# WorkshopEth.net
KiCad netlist of a schematic drawn in EasyEDA Pro
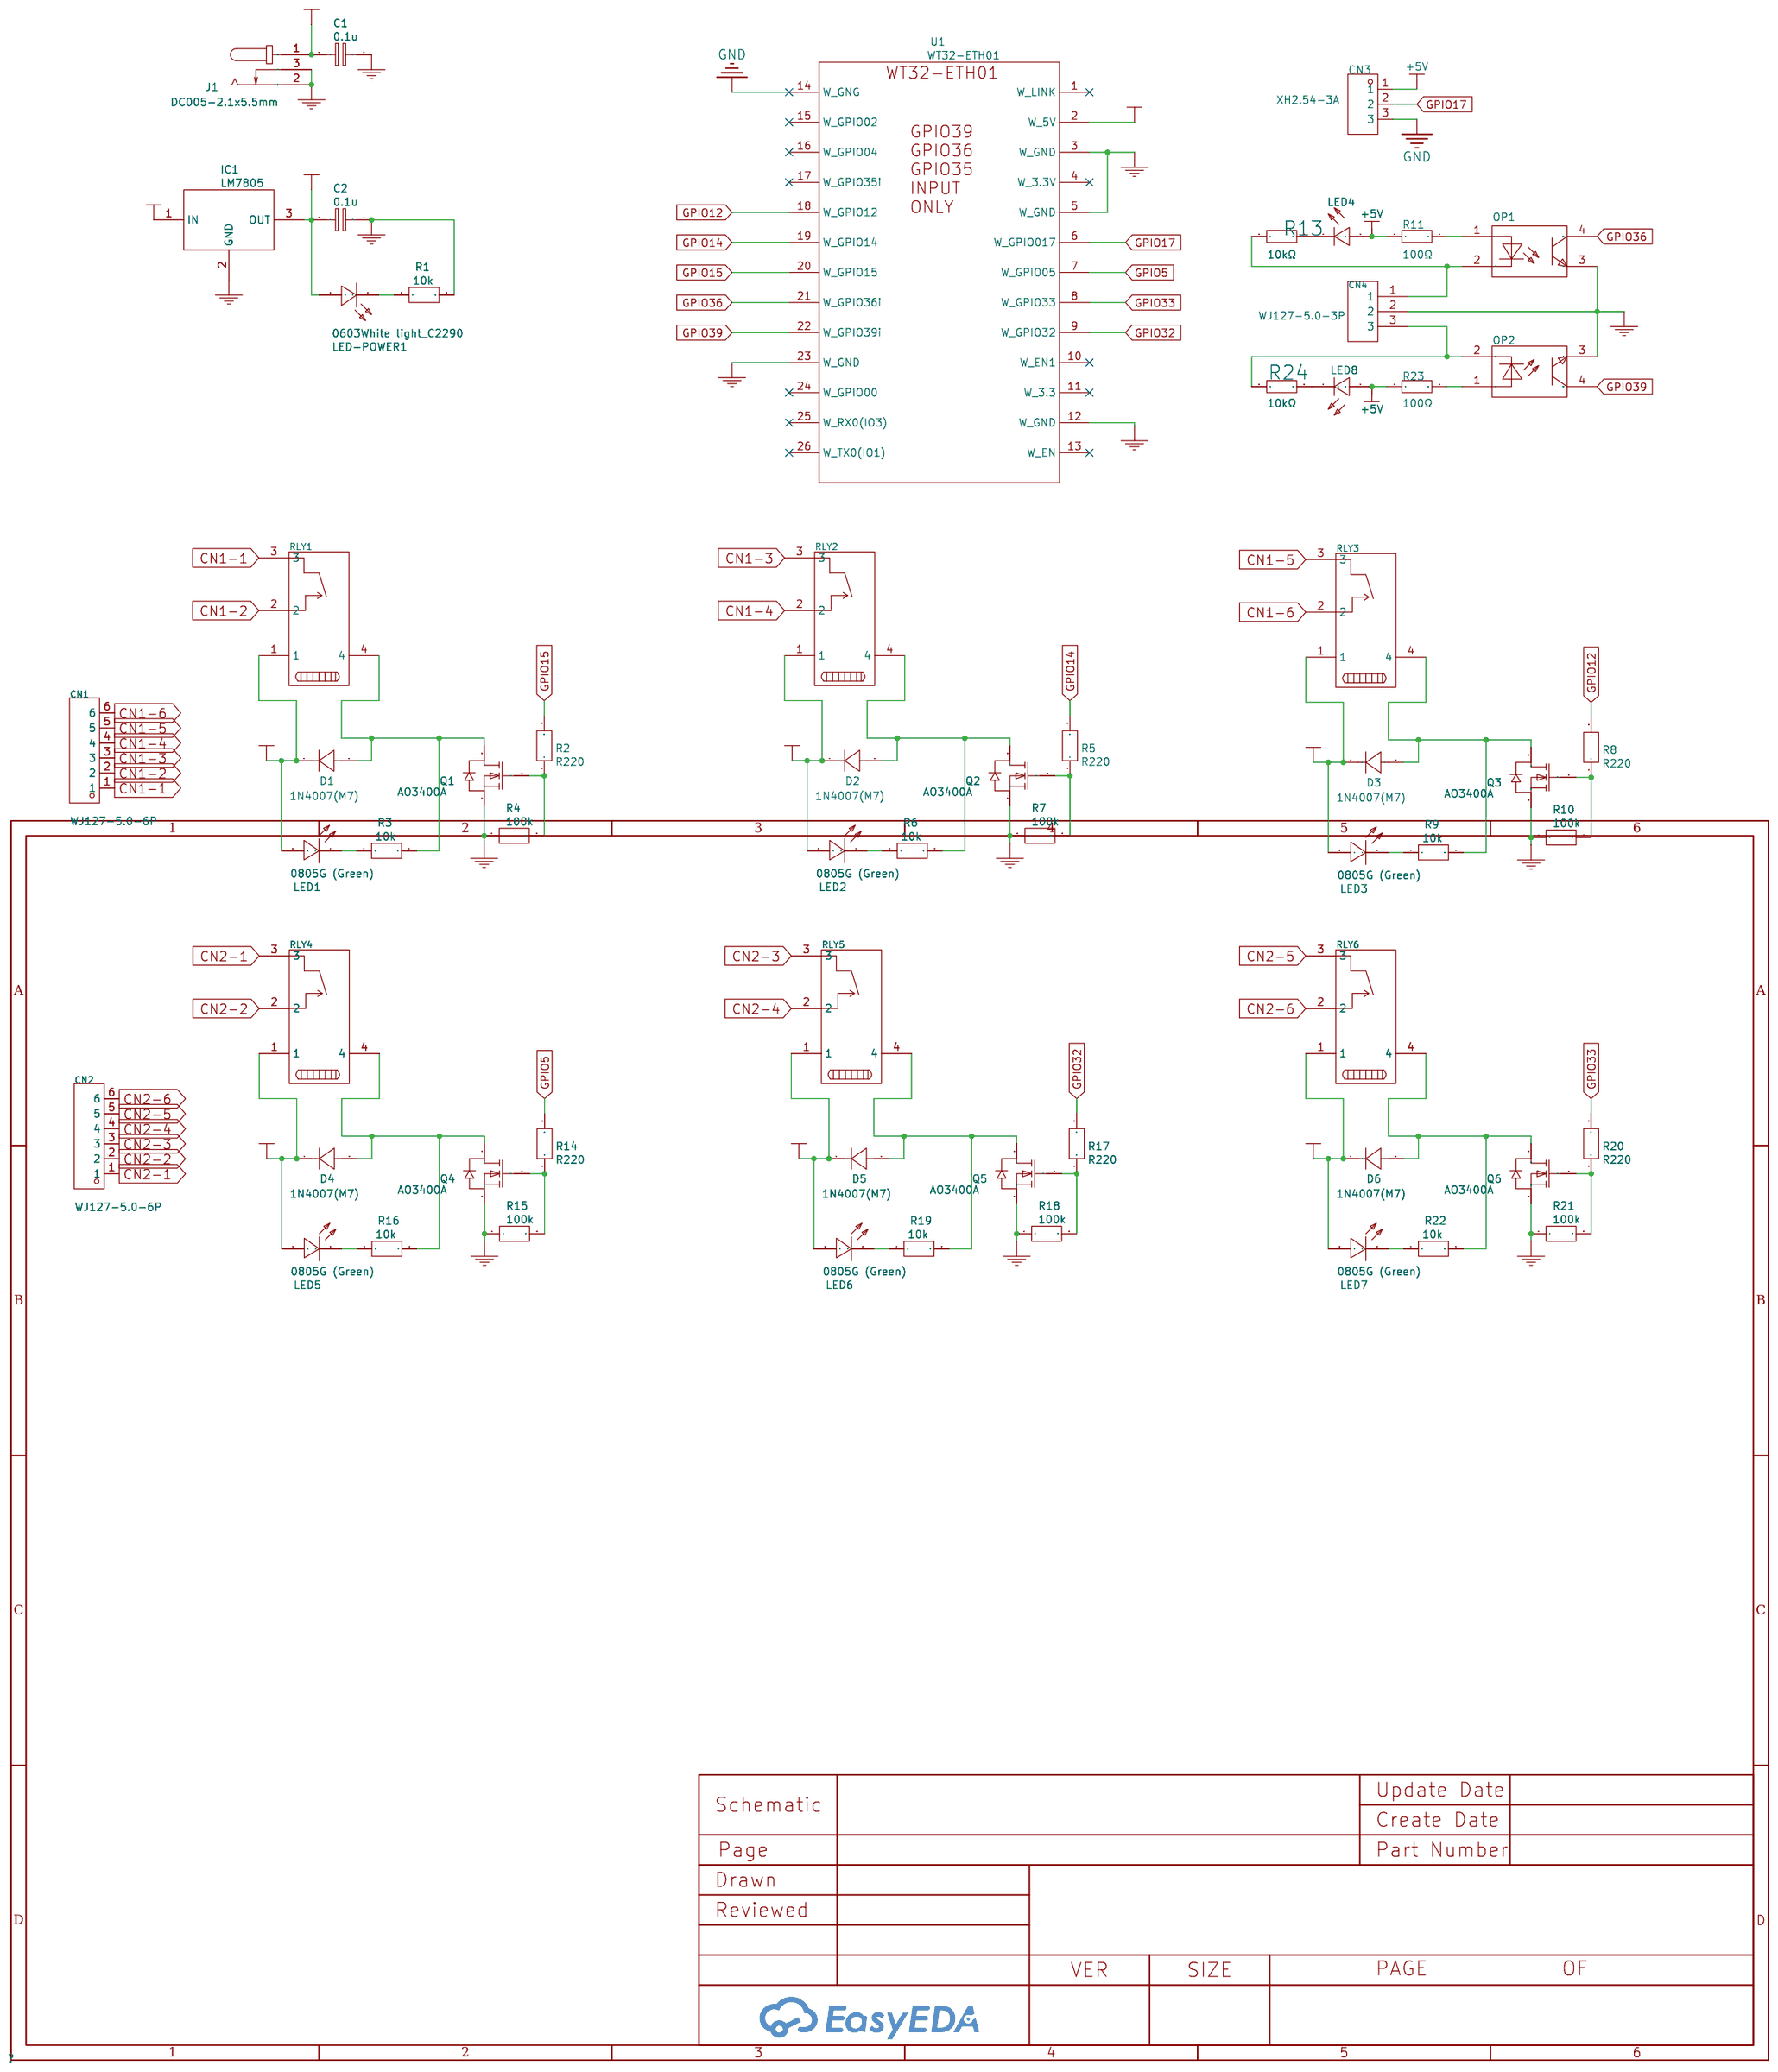
[diagram p0: schematic sheet]

(export (version "E")
  (design (tool "Eeschema 10.0.6"))
  (components
    (comp (ref "C1")
      (value "0.1u")
      (footprint "easyedapro:C0603")
      (fields
        (field (name "Manufacturer Part") "CL05B104KO5NNNC")
        (field (name "Manufacturer") "SAMSUNG(三星)")
      )
      (libsource (lib "easyedapro") (part "0.1u"))
    )
    (comp (ref "C2")
      (value "0.1u")
      (footprint "easyedapro:C0603")
      (fields
        (field (name "Manufacturer Part") "CL05B104KO5NNNC")
        (field (name "Manufacturer") "SAMSUNG(三星)")
      )
      (libsource (lib "easyedapro") (part "0.1u"))
    )
    (comp (ref "CN1")
      (value "WJ127-5.0-6P")
      (footprint "easyedapro:CONN-TH_6P-P5.00_WJ127-5.0-6P")
      (fields (field (name "Manufacturer") "KANGNEX(康奈克斯电气)"))
      (libsource (lib "easyedapro") (part "WJ127-5.0-6P"))
    )
    (comp (ref "CN2")
      (value "WJ127-5.0-6P")
      (footprint "easyedapro:CONN-TH_6P-P5.00_WJ127-5.0-6P")
      (fields (field (name "Manufacturer") "KANGNEX(康奈克斯电气)"))
      (libsource (lib "easyedapro") (part "WJ127-5.0-6P"))
    )
    (comp (ref "CN3")
      (value "XH2.54-3A")
      (footprint "easyedapro:CONN-TH_3P-P2.50_HCTL_XH-3A-L")
      (libsource (lib "easyedapro") (part "XH2.54-3A"))
    )
    (comp (ref "CN4")
      (value "WJ127-5.0-3P")
      (footprint "easyedapro:CONN-TH_3P-P5.00_WJ127-5.0-3P")
      (fields (field (name "Manufacturer") "KANGNEX(康奈克斯电气)"))
      (libsource (lib "easyedapro") (part "WJ127-5.0-3P"))
    )
    (comp (ref "D1")
      (value "1N4007(M7)")
      (footprint "easyedapro:SMA_L4.3-W2.7-LS5.1-RD")
      (fields (field (name "Manufacturer") "UMW(友台半导体)"))
      (libsource (lib "easyedapro") (part "1N4007(M7)"))
    )
    (comp (ref "D2")
      (value "1N4007(M7)")
      (footprint "easyedapro:SMA_L4.3-W2.7-LS5.1-RD")
      (fields (field (name "Manufacturer") "UMW(友台半导体)"))
      (libsource (lib "easyedapro") (part "1N4007(M7)"))
    )
    (comp (ref "D3")
      (value "1N4007(M7)")
      (footprint "easyedapro:SMA_L4.3-W2.7-LS5.1-RD")
      (fields (field (name "Manufacturer") "UMW(友台半导体)"))
      (libsource (lib "easyedapro") (part "1N4007(M7)"))
    )
    (comp (ref "D4")
      (value "1N4007(M7)")
      (footprint "easyedapro:SMA_L4.3-W2.7-LS5.1-RD")
      (fields (field (name "Manufacturer") "UMW(友台半导体)"))
      (libsource (lib "easyedapro") (part "1N4007(M7)"))
    )
    (comp (ref "D5")
      (value "1N4007(M7)")
      (footprint "easyedapro:SMA_L4.3-W2.7-LS5.1-RD")
      (fields (field (name "Manufacturer") "UMW(友台半导体)"))
      (libsource (lib "easyedapro") (part "1N4007(M7)"))
    )
    (comp (ref "D6")
      (value "1N4007(M7)")
      (footprint "easyedapro:SMA_L4.3-W2.7-LS5.1-RD")
      (fields (field (name "Manufacturer") "UMW(友台半导体)"))
      (libsource (lib "easyedapro") (part "1N4007(M7)"))
    )
    (comp (ref "IC1")
      (value "LM7805")
      (footprint "easyedapro:LM7805")
      (libsource (lib "easyedapro") (part "LM7805"))
    )
    (comp (ref "J1")
      (value "DC005-2.1x5.5mm")
      (footprint "easyedapro:DC-IN-TH_POWER-JACK")
      (fields (field (name "Manufacturer Part") "POWER-JACK") (field (name "Manufacturer") "索峰"))
      (libsource (lib "easyedapro") (part "DC005-2.1x5.5mm"))
    )
    (comp (ref "LED-POWER1")
      (value "0603White light_C2290")
      (footprint "easyedapro:LED0603-R-RD_WHITE")
      (fields (field (name "Manufacturer Part") "KT-0603W") (field (name "Manufacturer") "KENTO"))
      (libsource (lib "easyedapro") (part "0603White light_C2290"))
    )
    (comp (ref "LED1")
      (value "0805G (Green)")
      (footprint "easyedapro:LED0805-RD_GREEN")
      (fields (field (name "Manufacturer") "KENTO"))
      (libsource (lib "easyedapro") (part "0805G (Green)"))
    )
    (comp (ref "LED2")
      (value "0805G (Green)")
      (footprint "easyedapro:LED0805-RD_GREEN")
      (fields (field (name "Manufacturer") "KENTO"))
      (libsource (lib "easyedapro") (part "0805G (Green)"))
    )
    (comp (ref "LED3")
      (value "0805G (Green)")
      (footprint "easyedapro:LED0805-RD_GREEN")
      (fields (field (name "Manufacturer") "KENTO"))
      (libsource (lib "easyedapro") (part "0805G (Green)"))
    )
    (comp (ref "LED4")
      (value "19-213/Y2C-CQ2R2L/3T(CY)")
      (footprint "easyedapro:LED0603-RD-YELLOW")
      (fields (field (name "Manufacturer") "EVERLIGHT(亿光)"))
      (libsource (lib "easyedapro") (part "19-213/Y2C-CQ2R2L/3T(CY)"))
    )
    (comp (ref "LED5")
      (value "0805G (Green)")
      (footprint "easyedapro:LED0805-RD_GREEN")
      (fields (field (name "Manufacturer") "KENTO"))
      (libsource (lib "easyedapro") (part "0805G (Green)"))
    )
    (comp (ref "LED6")
      (value "0805G (Green)")
      (footprint "easyedapro:LED0805-RD_GREEN")
      (fields (field (name "Manufacturer") "KENTO"))
      (libsource (lib "easyedapro") (part "0805G (Green)"))
    )
    (comp (ref "LED7")
      (value "0805G (Green)")
      (footprint "easyedapro:LED0805-RD_GREEN")
      (fields (field (name "Manufacturer") "KENTO"))
      (libsource (lib "easyedapro") (part "0805G (Green)"))
    )
    (comp (ref "LED8")
      (value "19-213/Y2C-CQ2R2L/3T(CY)")
      (footprint "easyedapro:LED0603-RD-YELLOW")
      (fields (field (name "Manufacturer") "EVERLIGHT(亿光)"))
      (libsource (lib "easyedapro") (part "19-213/Y2C-CQ2R2L/3T(CY)"))
    )
    (comp (ref "OP1")
      (value "EL817S1(C)(TU)-F")
      (footprint "easyedapro:OPTO-SMD-4_L4.6-W6.5-P2.54-LS10.3-TL")
      (fields (field (name "Manufacturer") "EVERLIGHT(亿光)"))
      (libsource (lib "easyedapro") (part "EL817S1(C)(TU)-F"))
    )
    (comp (ref "OP2")
      (value "EL817S1(C)(TU)-F")
      (footprint "easyedapro:OPTO-SMD-4_L4.6-W6.5-P2.54-LS10.3-TL")
      (fields (field (name "Manufacturer") "EVERLIGHT(亿光)"))
      (libsource (lib "easyedapro") (part "EL817S1(C)(TU)-F"))
    )
    (comp (ref "Q1")
      (value "AO3400A")
      (footprint "easyedapro:SOT-23-3_L2.9-W1.6-P1.90-LS2.8-BR")
      (fields (field (name "Manufacturer") "AOS"))
      (libsource (lib "easyedapro") (part "AO3400A"))
    )
    (comp (ref "Q2")
      (value "AO3400A")
      (footprint "easyedapro:SOT-23-3_L2.9-W1.6-P1.90-LS2.8-BR")
      (fields (field (name "Manufacturer") "AOS"))
      (libsource (lib "easyedapro") (part "AO3400A"))
    )
    (comp (ref "Q3")
      (value "AO3400A")
      (footprint "easyedapro:SOT-23-3_L2.9-W1.6-P1.90-LS2.8-BR")
      (fields (field (name "Manufacturer") "AOS"))
      (libsource (lib "easyedapro") (part "AO3400A"))
    )
    (comp (ref "Q4")
      (value "AO3400A")
      (footprint "easyedapro:SOT-23-3_L2.9-W1.6-P1.90-LS2.8-BR")
      (fields (field (name "Manufacturer") "AOS"))
      (libsource (lib "easyedapro") (part "AO3400A"))
    )
    (comp (ref "Q5")
      (value "AO3400A")
      (footprint "easyedapro:SOT-23-3_L2.9-W1.6-P1.90-LS2.8-BR")
      (fields (field (name "Manufacturer") "AOS"))
      (libsource (lib "easyedapro") (part "AO3400A"))
    )
    (comp (ref "Q6")
      (value "AO3400A")
      (footprint "easyedapro:SOT-23-3_L2.9-W1.6-P1.90-LS2.8-BR")
      (fields (field (name "Manufacturer") "AOS"))
      (libsource (lib "easyedapro") (part "AO3400A"))
    )
    (comp (ref "R1")
      (value "10k")
      (footprint "easyedapro:R0603")
      (fields
        (field (name "Manufacturer Part") "0603WAF1002T5E")
        (field (name "Manufacturer") "UNI-ROYAL(厚声)")
      )
      (libsource (lib "easyedapro") (part "10k"))
    )
    (comp (ref "R2")
      (value "R220")
      (footprint "easyedapro:R0603")
      (fields
        (field (name "Manufacturer Part") "0603WAF2200T5E")
        (field (name "Manufacturer") "UNI-ROYAL(厚声)")
      )
      (libsource (lib "easyedapro") (part "R220"))
    )
    (comp (ref "R3")
      (value "10k")
      (footprint "easyedapro:R0603")
      (fields
        (field (name "Manufacturer Part") "0603WAF1002T5E")
        (field (name "Manufacturer") "UNI-ROYAL(厚声)")
      )
      (libsource (lib "easyedapro") (part "10k"))
    )
    (comp (ref "R4")
      (value "100k")
      (footprint "easyedapro:R0603")
      (fields
        (field (name "Manufacturer Part") "0603WAF1003T5E")
        (field (name "Manufacturer") "UNI-ROYAL(厚声)")
      )
      (libsource (lib "easyedapro") (part "100k"))
    )
    (comp (ref "R5")
      (value "R220")
      (footprint "easyedapro:R0603")
      (fields
        (field (name "Manufacturer Part") "0603WAF2200T5E")
        (field (name "Manufacturer") "UNI-ROYAL(厚声)")
      )
      (libsource (lib "easyedapro") (part "R220"))
    )
    (comp (ref "R6")
      (value "10k")
      (footprint "easyedapro:R0603")
      (fields
        (field (name "Manufacturer Part") "0603WAF1002T5E")
        (field (name "Manufacturer") "UNI-ROYAL(厚声)")
      )
      (libsource (lib "easyedapro") (part "10k"))
    )
    (comp (ref "R7")
      (value "100k")
      (footprint "easyedapro:R0603")
      (fields
        (field (name "Manufacturer Part") "0603WAF1003T5E")
        (field (name "Manufacturer") "UNI-ROYAL(厚声)")
      )
      (libsource (lib "easyedapro") (part "100k"))
    )
    (comp (ref "R8")
      (value "R220")
      (footprint "easyedapro:R0603")
      (fields
        (field (name "Manufacturer Part") "0603WAF2200T5E")
        (field (name "Manufacturer") "UNI-ROYAL(厚声)")
      )
      (libsource (lib "easyedapro") (part "R220"))
    )
    (comp (ref "R9")
      (value "10k")
      (footprint "easyedapro:R0603")
      (fields
        (field (name "Manufacturer Part") "0603WAF1002T5E")
        (field (name "Manufacturer") "UNI-ROYAL(厚声)")
      )
      (libsource (lib "easyedapro") (part "10k"))
    )
    (comp (ref "R10")
      (value "100k")
      (footprint "easyedapro:R0603")
      (fields
        (field (name "Manufacturer Part") "0603WAF1003T5E")
        (field (name "Manufacturer") "UNI-ROYAL(厚声)")
      )
      (libsource (lib "easyedapro") (part "100k"))
    )
    (comp (ref "R11")
      (value "100Ω")
      (footprint "easyedapro:R0805")
      (fields
        (field (name "Manufacturer Part") "0805W8F1000T5E")
        (field (name "Manufacturer") "UNI-ROYAL(厚声)")
      )
      (libsource (lib "easyedapro") (part "0805W8F1000T5E"))
    )
    (comp (ref "R13")
      (value "10kΩ")
      (footprint "easyedapro:R0603")
      (fields
        (field (name "Manufacturer Part") "0603WAF1002T5E")
        (field (name "Manufacturer") "UNI-ROYAL(厚声)")
      )
      (libsource (lib "easyedapro") (part "0603WAF1002T5E"))
    )
    (comp (ref "R14")
      (value "R220")
      (footprint "easyedapro:R0603")
      (fields
        (field (name "Manufacturer Part") "0603WAF2200T5E")
        (field (name "Manufacturer") "UNI-ROYAL(厚声)")
      )
      (libsource (lib "easyedapro") (part "R220"))
    )
    (comp (ref "R15")
      (value "100k")
      (footprint "easyedapro:R0603")
      (fields
        (field (name "Manufacturer Part") "0603WAF1003T5E")
        (field (name "Manufacturer") "UNI-ROYAL(厚声)")
      )
      (libsource (lib "easyedapro") (part "100k"))
    )
    (comp (ref "R16")
      (value "10k")
      (footprint "easyedapro:R0603")
      (fields
        (field (name "Manufacturer Part") "0603WAF1002T5E")
        (field (name "Manufacturer") "UNI-ROYAL(厚声)")
      )
      (libsource (lib "easyedapro") (part "10k"))
    )
    (comp (ref "R17")
      (value "R220")
      (footprint "easyedapro:R0603")
      (fields
        (field (name "Manufacturer Part") "0603WAF2200T5E")
        (field (name "Manufacturer") "UNI-ROYAL(厚声)")
      )
      (libsource (lib "easyedapro") (part "R220"))
    )
    (comp (ref "R18")
      (value "100k")
      (footprint "easyedapro:R0603")
      (fields
        (field (name "Manufacturer Part") "0603WAF1003T5E")
        (field (name "Manufacturer") "UNI-ROYAL(厚声)")
      )
      (libsource (lib "easyedapro") (part "100k"))
    )
    (comp (ref "R19")
      (value "10k")
      (footprint "easyedapro:R0603")
      (fields
        (field (name "Manufacturer Part") "0603WAF1002T5E")
        (field (name "Manufacturer") "UNI-ROYAL(厚声)")
      )
      (libsource (lib "easyedapro") (part "10k"))
    )
    (comp (ref "R20")
      (value "R220")
      (footprint "easyedapro:R0603")
      (fields
        (field (name "Manufacturer Part") "0603WAF2200T5E")
        (field (name "Manufacturer") "UNI-ROYAL(厚声)")
      )
      (libsource (lib "easyedapro") (part "R220"))
    )
    (comp (ref "R21")
      (value "100k")
      (footprint "easyedapro:R0603")
      (fields
        (field (name "Manufacturer Part") "0603WAF1003T5E")
        (field (name "Manufacturer") "UNI-ROYAL(厚声)")
      )
      (libsource (lib "easyedapro") (part "100k"))
    )
    (comp (ref "R22")
      (value "10k")
      (footprint "easyedapro:R0603")
      (fields
        (field (name "Manufacturer Part") "0603WAF1002T5E")
        (field (name "Manufacturer") "UNI-ROYAL(厚声)")
      )
      (libsource (lib "easyedapro") (part "10k"))
    )
    (comp (ref "R23")
      (value "100Ω")
      (footprint "easyedapro:R0805")
      (fields
        (field (name "Manufacturer Part") "0805W8F1000T5E")
        (field (name "Manufacturer") "UNI-ROYAL(厚声)")
      )
      (libsource (lib "easyedapro") (part "0805W8F1000T5E"))
    )
    (comp (ref "R24")
      (value "10kΩ")
      (footprint "easyedapro:R0603")
      (fields
        (field (name "Manufacturer Part") "0603WAF1002T5E")
        (field (name "Manufacturer") "UNI-ROYAL(厚声)")
      )
      (libsource (lib "easyedapro") (part "0603WAF1002T5E"))
    )
    (comp (ref "RLY1")
      (value "G5NB-1A-E-DC5V")
      (footprint "easyedapro:RELAY-TH_G5NB-1A-E-DCXX")
      (fields (field (name "Manufacturer") "OMRON(欧姆龙)"))
      (libsource (lib "easyedapro") (part "G5NB-1A-E-DC5V"))
    )
    (comp (ref "RLY2")
      (value "G5NB-1A-E-DC5V")
      (footprint "easyedapro:RELAY-TH_G5NB-1A-E-DCXX")
      (fields (field (name "Manufacturer") "OMRON(欧姆龙)"))
      (libsource (lib "easyedapro") (part "G5NB-1A-E-DC5V"))
    )
    (comp (ref "RLY3")
      (value "G5NB-1A-E-DC5V")
      (footprint "easyedapro:RELAY-TH_G5NB-1A-E-DCXX")
      (fields (field (name "Manufacturer") "OMRON(欧姆龙)"))
      (libsource (lib "easyedapro") (part "G5NB-1A-E-DC5V"))
    )
    (comp (ref "RLY4")
      (value "G5NB-1A-E-DC5V")
      (footprint "easyedapro:RELAY-TH_G5NB-1A-E-DCXX")
      (fields (field (name "Manufacturer") "OMRON(欧姆龙)"))
      (libsource (lib "easyedapro") (part "G5NB-1A-E-DC5V"))
    )
    (comp (ref "RLY5")
      (value "G5NB-1A-E-DC5V")
      (footprint "easyedapro:RELAY-TH_G5NB-1A-E-DCXX")
      (fields (field (name "Manufacturer") "OMRON(欧姆龙)"))
      (libsource (lib "easyedapro") (part "G5NB-1A-E-DC5V"))
    )
    (comp (ref "RLY6")
      (value "G5NB-1A-E-DC5V")
      (footprint "easyedapro:RELAY-TH_G5NB-1A-E-DCXX")
      (fields (field (name "Manufacturer") "OMRON(欧姆龙)"))
      (libsource (lib "easyedapro") (part "G5NB-1A-E-DC5V"))
    )
    (comp (ref "U1")
      (value "WT32-ETH01")
      (footprint "easyedapro:WT32-ETH01-M")
      (fields (field (name "Manufacturer") "Wireless-Tag"))
      (libsource (lib "easyedapro") (part "WT32-ETH01"))
    )
  )
  (nets
    (net (code "1") (name "+5V") (class "Default")
      (node (ref "C2") (pin "1") (pinfunction "1_1") (pintype "unspecified"))
      (node (ref "CN3") (pin "1") (pinfunction "1_1") (pintype "unspecified"))
      (node (ref "D1") (pin "1") (pinfunction "K_1") (pintype "unspecified"))
      (node (ref "D2") (pin "1") (pinfunction "K_1") (pintype "unspecified"))
      (node (ref "D3") (pin "1") (pinfunction "K_1") (pintype "unspecified"))
      (node (ref "D4") (pin "1") (pinfunction "K_1") (pintype "unspecified"))
      (node (ref "D5") (pin "1") (pinfunction "K_1") (pintype "unspecified"))
      (node (ref "D6") (pin "1") (pinfunction "K_1") (pintype "unspecified"))
      (node (ref "IC1") (pin "3") (pinfunction "OUT_3") (pintype "unspecified"))
      (node (ref "LED-POWER1") (pin "1") (pinfunction "A_1") (pintype "unspecified"))
      (node (ref "LED1") (pin "2") (pinfunction "A_2") (pintype "unspecified"))
      (node (ref "LED2") (pin "2") (pinfunction "A_2") (pintype "unspecified"))
      (node (ref "LED3") (pin "2") (pinfunction "A_2") (pintype "unspecified"))
      (node (ref "LED4") (pin "2") (pinfunction "A_2") (pintype "input"))
      (node (ref "LED5") (pin "2") (pinfunction "A_2") (pintype "unspecified"))
      (node (ref "LED6") (pin "2") (pinfunction "A_2") (pintype "unspecified"))
      (node (ref "LED7") (pin "2") (pinfunction "A_2") (pintype "unspecified"))
      (node (ref "LED8") (pin "2") (pinfunction "A_2") (pintype "input"))
      (node (ref "R11") (pin "1") (pinfunction "1_1") (pintype "input"))
      (node (ref "R23") (pin "1") (pinfunction "1_1") (pintype "input"))
      (node (ref "RLY1") (pin "1") (pinfunction "1_1") (pintype "input"))
      (node (ref "RLY2") (pin "1") (pinfunction "1_1") (pintype "input"))
      (node (ref "RLY3") (pin "1") (pinfunction "1_1") (pintype "input"))
      (node (ref "RLY4") (pin "1") (pinfunction "1_1") (pintype "input"))
      (node (ref "RLY5") (pin "1") (pinfunction "1_1") (pintype "input"))
      (node (ref "RLY6") (pin "1") (pinfunction "1_1") (pintype "input"))
      (node (ref "U1") (pin "2") (pinfunction "W_5V_2") (pintype "unspecified"))
    )
    (net (code "2") (name "CN1-1") (class "Default")
      (node (ref "CN1") (pin "1") (pinfunction "1_1") (pintype "input"))
      (node (ref "RLY1") (pin "3") (pinfunction "3_3") (pintype "input"))
    )
    (net (code "3") (name "CN1-2") (class "Default")
      (node (ref "CN1") (pin "2") (pinfunction "2_2") (pintype "input"))
      (node (ref "RLY1") (pin "2") (pinfunction "2_2") (pintype "input"))
    )
    (net (code "4") (name "CN1-3") (class "Default")
      (node (ref "CN1") (pin "3") (pinfunction "3_3") (pintype "input"))
      (node (ref "RLY2") (pin "3") (pinfunction "3_3") (pintype "input"))
    )
    (net (code "5") (name "CN1-4") (class "Default")
      (node (ref "CN1") (pin "4") (pinfunction "4_4") (pintype "input"))
      (node (ref "RLY2") (pin "2") (pinfunction "2_2") (pintype "input"))
    )
    (net (code "6") (name "CN1-5") (class "Default")
      (node (ref "CN1") (pin "5") (pinfunction "5_5") (pintype "input"))
      (node (ref "RLY3") (pin "3") (pinfunction "3_3") (pintype "input"))
    )
    (net (code "7") (name "CN1-6") (class "Default")
      (node (ref "CN1") (pin "6") (pinfunction "6_6") (pintype "input"))
      (node (ref "RLY3") (pin "2") (pinfunction "2_2") (pintype "input"))
    )
    (net (code "8") (name "CN2-1") (class "Default")
      (node (ref "CN2") (pin "1") (pinfunction "1_1") (pintype "input"))
      (node (ref "RLY4") (pin "3") (pinfunction "3_3") (pintype "input"))
    )
    (net (code "9") (name "CN2-2") (class "Default")
      (node (ref "CN2") (pin "2") (pinfunction "2_2") (pintype "input"))
      (node (ref "RLY4") (pin "2") (pinfunction "2_2") (pintype "input"))
    )
    (net (code "10") (name "CN2-3") (class "Default")
      (node (ref "CN2") (pin "3") (pinfunction "3_3") (pintype "input"))
      (node (ref "RLY5") (pin "3") (pinfunction "3_3") (pintype "input"))
    )
    (net (code "11") (name "CN2-4") (class "Default")
      (node (ref "CN2") (pin "4") (pinfunction "4_4") (pintype "input"))
      (node (ref "RLY5") (pin "2") (pinfunction "2_2") (pintype "input"))
    )
    (net (code "12") (name "CN2-5") (class "Default")
      (node (ref "CN2") (pin "5") (pinfunction "5_5") (pintype "input"))
      (node (ref "RLY6") (pin "3") (pinfunction "3_3") (pintype "input"))
    )
    (net (code "13") (name "CN2-6") (class "Default")
      (node (ref "CN2") (pin "6") (pinfunction "6_6") (pintype "input"))
      (node (ref "RLY6") (pin "2") (pinfunction "2_2") (pintype "input"))
    )
    (net (code "14") (name "GND") (class "Default")
      (node (ref "C1") (pin "2") (pinfunction "2_2") (pintype "unspecified"))
      (node (ref "C2") (pin "2") (pinfunction "2_2") (pintype "unspecified"))
      (node (ref "CN3") (pin "3") (pinfunction "3_3") (pintype "unspecified"))
      (node (ref "CN4") (pin "2") (pinfunction "2_2") (pintype "input"))
      (node (ref "IC1") (pin "2") (pinfunction "GND_2") (pintype "unspecified"))
      (node (ref "J1") (pin "2") (pinfunction "GND_2") (pintype "unspecified"))
      (node (ref "J1") (pin "3") (pinfunction "3_3") (pintype "unspecified"))
      (node (ref "OP1") (pin "3") (pinfunction "EM_3") (pintype "unspecified"))
      (node (ref "OP2") (pin "3") (pinfunction "EM_3") (pintype "unspecified"))
      (node (ref "Q1") (pin "2") (pinfunction "S_2") (pintype "unspecified"))
      (node (ref "Q2") (pin "2") (pinfunction "S_2") (pintype "unspecified"))
      (node (ref "Q3") (pin "2") (pinfunction "S_2") (pintype "unspecified"))
      (node (ref "Q4") (pin "2") (pinfunction "S_2") (pintype "unspecified"))
      (node (ref "Q5") (pin "2") (pinfunction "S_2") (pintype "unspecified"))
      (node (ref "Q6") (pin "2") (pinfunction "S_2") (pintype "unspecified"))
      (node (ref "R1") (pin "2") (pinfunction "2_2") (pintype "unspecified"))
      (node (ref "R10") (pin "1") (pinfunction "1_1") (pintype "unspecified"))
      (node (ref "R15") (pin "1") (pinfunction "1_1") (pintype "unspecified"))
      (node (ref "R18") (pin "1") (pinfunction "1_1") (pintype "unspecified"))
      (node (ref "R21") (pin "1") (pinfunction "1_1") (pintype "unspecified"))
      (node (ref "R4") (pin "1") (pinfunction "1_1") (pintype "unspecified"))
      (node (ref "R7") (pin "1") (pinfunction "1_1") (pintype "unspecified"))
      (node (ref "U1") (pin "12") (pinfunction "W_GND_12") (pintype "unspecified"))
      (node (ref "U1") (pin "14") (pinfunction "W_GNG_14") (pintype "unspecified"))
      (node (ref "U1") (pin "23") (pinfunction "W_GND_23") (pintype "unspecified"))
      (node (ref "U1") (pin "3") (pinfunction "W_GND_3") (pintype "unspecified"))
      (node (ref "U1") (pin "5") (pinfunction "W_GND_5") (pintype "unspecified"))
    )
    (net (code "15") (name "GPIO5") (class "Default")
      (node (ref "R14") (pin "2") (pinfunction "2_2") (pintype "unspecified"))
      (node (ref "U1") (pin "7") (pinfunction "W_GPIO05_7") (pintype "unspecified"))
    )
    (net (code "16") (name "GPIO12") (class "Default")
      (node (ref "R8") (pin "2") (pinfunction "2_2") (pintype "unspecified"))
      (node (ref "U1") (pin "18") (pinfunction "W_GPIO12_18") (pintype "unspecified"))
    )
    (net (code "17") (name "GPIO14") (class "Default")
      (node (ref "R5") (pin "2") (pinfunction "2_2") (pintype "unspecified"))
      (node (ref "U1") (pin "19") (pinfunction "W_GPIO14_19") (pintype "unspecified"))
    )
    (net (code "18") (name "GPIO15") (class "Default")
      (node (ref "R2") (pin "2") (pinfunction "2_2") (pintype "unspecified"))
      (node (ref "U1") (pin "20") (pinfunction "W_GPIO15_20") (pintype "unspecified"))
    )
    (net (code "19") (name "GPIO17") (class "Default")
      (node (ref "CN3") (pin "2") (pinfunction "2_2") (pintype "unspecified"))
      (node (ref "U1") (pin "6") (pinfunction "W_GPIO017_6") (pintype "unspecified"))
    )
    (net (code "20") (name "GPIO32") (class "Default")
      (node (ref "R17") (pin "2") (pinfunction "2_2") (pintype "unspecified"))
      (node (ref "U1") (pin "9") (pinfunction "W_GPIO32_9") (pintype "unspecified"))
    )
    (net (code "21") (name "GPIO33") (class "Default")
      (node (ref "R20") (pin "2") (pinfunction "2_2") (pintype "unspecified"))
      (node (ref "U1") (pin "8") (pinfunction "W_GPIO33_8") (pintype "unspecified"))
    )
    (net (code "22") (name "GPIO36") (class "Default")
      (node (ref "OP1") (pin "4") (pinfunction "COL_4") (pintype "unspecified"))
      (node (ref "U1") (pin "21") (pinfunction "W_GPIO36i_21") (pintype "unspecified"))
    )
    (net (code "23") (name "GPIO39") (class "Default")
      (node (ref "OP2") (pin "4") (pinfunction "COL_4") (pintype "unspecified"))
      (node (ref "U1") (pin "22") (pinfunction "W_GPIO39i_22") (pintype "unspecified"))
    )
    (net (code "24") (name "Net-(D1-A)") (class "Default")
      (node (ref "D1") (pin "2") (pinfunction "A_2") (pintype "unspecified"))
      (node (ref "Q1") (pin "3") (pinfunction "D_3") (pintype "unspecified"))
      (node (ref "R3") (pin "2") (pinfunction "2_2") (pintype "unspecified"))
      (node (ref "RLY1") (pin "4") (pinfunction "4_4") (pintype "input"))
    )
    (net (code "25") (name "Net-(D2-A)") (class "Default")
      (node (ref "D2") (pin "2") (pinfunction "A_2") (pintype "unspecified"))
      (node (ref "Q2") (pin "3") (pinfunction "D_3") (pintype "unspecified"))
      (node (ref "R6") (pin "2") (pinfunction "2_2") (pintype "unspecified"))
      (node (ref "RLY2") (pin "4") (pinfunction "4_4") (pintype "input"))
    )
    (net (code "26") (name "Net-(D3-A)") (class "Default")
      (node (ref "D3") (pin "2") (pinfunction "A_2") (pintype "unspecified"))
      (node (ref "Q3") (pin "3") (pinfunction "D_3") (pintype "unspecified"))
      (node (ref "R9") (pin "2") (pinfunction "2_2") (pintype "unspecified"))
      (node (ref "RLY3") (pin "4") (pinfunction "4_4") (pintype "input"))
    )
    (net (code "27") (name "Net-(D4-A)") (class "Default")
      (node (ref "D4") (pin "2") (pinfunction "A_2") (pintype "unspecified"))
      (node (ref "Q4") (pin "3") (pinfunction "D_3") (pintype "unspecified"))
      (node (ref "R16") (pin "2") (pinfunction "2_2") (pintype "unspecified"))
      (node (ref "RLY4") (pin "4") (pinfunction "4_4") (pintype "input"))
    )
    (net (code "28") (name "Net-(D5-A)") (class "Default")
      (node (ref "D5") (pin "2") (pinfunction "A_2") (pintype "unspecified"))
      (node (ref "Q5") (pin "3") (pinfunction "D_3") (pintype "unspecified"))
      (node (ref "R19") (pin "2") (pinfunction "2_2") (pintype "unspecified"))
      (node (ref "RLY5") (pin "4") (pinfunction "4_4") (pintype "input"))
    )
    (net (code "29") (name "Net-(D6-A)") (class "Default")
      (node (ref "D6") (pin "2") (pinfunction "A_2") (pintype "unspecified"))
      (node (ref "Q6") (pin "3") (pinfunction "D_3") (pintype "unspecified"))
      (node (ref "R22") (pin "2") (pinfunction "2_2") (pintype "unspecified"))
      (node (ref "RLY6") (pin "4") (pinfunction "4_4") (pintype "input"))
    )
    (net (code "30") (name "Net-(LED-POWER1-K)") (class "Default")
      (node (ref "LED-POWER1") (pin "2") (pinfunction "K_2") (pintype "unspecified"))
      (node (ref "R1") (pin "1") (pinfunction "1_1") (pintype "unspecified"))
    )
    (net (code "31") (name "Net-(LED1-K)") (class "Default")
      (node (ref "LED1") (pin "1") (pinfunction "K_1") (pintype "unspecified"))
      (node (ref "R3") (pin "1") (pinfunction "1_1") (pintype "unspecified"))
    )
    (net (code "32") (name "Net-(LED2-K)") (class "Default")
      (node (ref "LED2") (pin "1") (pinfunction "K_1") (pintype "unspecified"))
      (node (ref "R6") (pin "1") (pinfunction "1_1") (pintype "unspecified"))
    )
    (net (code "33") (name "Net-(LED3-K)") (class "Default")
      (node (ref "LED3") (pin "1") (pinfunction "K_1") (pintype "unspecified"))
      (node (ref "R9") (pin "1") (pinfunction "1_1") (pintype "unspecified"))
    )
    (net (code "34") (name "Net-(LED4-C)") (class "Default")
      (node (ref "LED4") (pin "1") (pinfunction "C_1") (pintype "input"))
      (node (ref "R13") (pin "2") (pinfunction "2_2") (pintype "input"))
    )
    (net (code "35") (name "Net-(LED5-K)") (class "Default")
      (node (ref "LED5") (pin "1") (pinfunction "K_1") (pintype "unspecified"))
      (node (ref "R16") (pin "1") (pinfunction "1_1") (pintype "unspecified"))
    )
    (net (code "36") (name "Net-(LED6-K)") (class "Default")
      (node (ref "LED6") (pin "1") (pinfunction "K_1") (pintype "unspecified"))
      (node (ref "R19") (pin "1") (pinfunction "1_1") (pintype "unspecified"))
    )
    (net (code "37") (name "Net-(LED7-K)") (class "Default")
      (node (ref "LED7") (pin "1") (pinfunction "K_1") (pintype "unspecified"))
      (node (ref "R22") (pin "1") (pinfunction "1_1") (pintype "unspecified"))
    )
    (net (code "38") (name "Net-(LED8-C)") (class "Default")
      (node (ref "LED8") (pin "1") (pinfunction "C_1") (pintype "input"))
      (node (ref "R24") (pin "2") (pinfunction "2_2") (pintype "input"))
    )
    (net (code "39") (name "Net-(OP1-AN)") (class "Default")
      (node (ref "OP1") (pin "1") (pinfunction "AN_1") (pintype "unspecified"))
      (node (ref "R11") (pin "2") (pinfunction "2_2") (pintype "input"))
    )
    (net (code "40") (name "Net-(OP1-CAT)") (class "Default")
      (node (ref "CN4") (pin "1") (pinfunction "1_1") (pintype "input"))
      (node (ref "OP1") (pin "2") (pinfunction "CAT_2") (pintype "unspecified"))
      (node (ref "R13") (pin "1") (pinfunction "1_1") (pintype "input"))
    )
    (net (code "41") (name "Net-(OP2-AN)") (class "Default")
      (node (ref "OP2") (pin "1") (pinfunction "AN_1") (pintype "unspecified"))
      (node (ref "R23") (pin "2") (pinfunction "2_2") (pintype "input"))
    )
    (net (code "42") (name "Net-(OP2-CAT)") (class "Default")
      (node (ref "CN4") (pin "3") (pinfunction "3_3") (pintype "input"))
      (node (ref "OP2") (pin "2") (pinfunction "CAT_2") (pintype "unspecified"))
      (node (ref "R24") (pin "1") (pinfunction "1_1") (pintype "input"))
    )
    (net (code "43") (name "Net-(Q1-G)") (class "Default")
      (node (ref "Q1") (pin "1") (pinfunction "G_1") (pintype "unspecified"))
      (node (ref "R2") (pin "1") (pinfunction "1_1") (pintype "unspecified"))
      (node (ref "R4") (pin "2") (pinfunction "2_2") (pintype "unspecified"))
    )
    (net (code "44") (name "Net-(Q2-G)") (class "Default")
      (node (ref "Q2") (pin "1") (pinfunction "G_1") (pintype "unspecified"))
      (node (ref "R5") (pin "1") (pinfunction "1_1") (pintype "unspecified"))
      (node (ref "R7") (pin "2") (pinfunction "2_2") (pintype "unspecified"))
    )
    (net (code "45") (name "Net-(Q3-G)") (class "Default")
      (node (ref "Q3") (pin "1") (pinfunction "G_1") (pintype "unspecified"))
      (node (ref "R10") (pin "2") (pinfunction "2_2") (pintype "unspecified"))
      (node (ref "R8") (pin "1") (pinfunction "1_1") (pintype "unspecified"))
    )
    (net (code "46") (name "Net-(Q4-G)") (class "Default")
      (node (ref "Q4") (pin "1") (pinfunction "G_1") (pintype "unspecified"))
      (node (ref "R14") (pin "1") (pinfunction "1_1") (pintype "unspecified"))
      (node (ref "R15") (pin "2") (pinfunction "2_2") (pintype "unspecified"))
    )
    (net (code "47") (name "Net-(Q5-G)") (class "Default")
      (node (ref "Q5") (pin "1") (pinfunction "G_1") (pintype "unspecified"))
      (node (ref "R17") (pin "1") (pinfunction "1_1") (pintype "unspecified"))
      (node (ref "R18") (pin "2") (pinfunction "2_2") (pintype "unspecified"))
    )
    (net (code "48") (name "Net-(Q6-G)") (class "Default")
      (node (ref "Q6") (pin "1") (pinfunction "G_1") (pintype "unspecified"))
      (node (ref "R20") (pin "1") (pinfunction "1_1") (pintype "unspecified"))
      (node (ref "R21") (pin "2") (pinfunction "2_2") (pintype "unspecified"))
    )
    (net (code "49") (name "VCC") (class "Default")
      (node (ref "C1") (pin "1") (pinfunction "1_1") (pintype "unspecified"))
      (node (ref "IC1") (pin "1") (pinfunction "IN_1") (pintype "unspecified"))
      (node (ref "J1") (pin "1") (pinfunction "VCC_1") (pintype "unspecified"))
    )
    (net (code "50") (name "unconnected-(U1-W_3.3-Pad11)") (class "Default")
      (node (ref "U1") (pin "11") (pinfunction "W_3.3_11") (pintype "unspecified+no_connect"))
    )
    (net (code "51") (name "unconnected-(U1-W_3.3V-Pad4)") (class "Default")
      (node (ref "U1") (pin "4") (pinfunction "W_3.3V_4") (pintype "unspecified+no_connect"))
    )
    (net (code "52") (name "unconnected-(U1-W_EN-Pad13)") (class "Default")
      (node (ref "U1") (pin "13") (pinfunction "W_EN_13") (pintype "unspecified+no_connect"))
    )
    (net (code "53") (name "unconnected-(U1-W_EN1-Pad10)") (class "Default")
      (node (ref "U1") (pin "10") (pinfunction "W_EN1_10") (pintype "unspecified+no_connect"))
    )
    (net (code "54") (name "unconnected-(U1-W_GPIO00-Pad24)") (class "Default")
      (node (ref "U1") (pin "24") (pinfunction "W_GPIO00_24") (pintype "unspecified+no_connect"))
    )
    (net (code "55") (name "unconnected-(U1-W_GPIO02-Pad15)") (class "Default")
      (node (ref "U1") (pin "15") (pinfunction "W_GPIO02_15") (pintype "unspecified+no_connect"))
    )
    (net (code "56") (name "unconnected-(U1-W_GPIO04-Pad16)") (class "Default")
      (node (ref "U1") (pin "16") (pinfunction "W_GPIO04_16") (pintype "unspecified+no_connect"))
    )
    (net (code "57") (name "unconnected-(U1-W_GPIO35i-Pad17)") (class "Default")
      (node (ref "U1") (pin "17") (pinfunction "W_GPIO35i_17") (pintype "unspecified+no_connect"))
    )
    (net (code "58") (name "unconnected-(U1-W_LINK-Pad1)") (class "Default")
      (node (ref "U1") (pin "1") (pinfunction "W_LINK_1") (pintype "unspecified+no_connect"))
    )
    (net (code "59") (name "unconnected-(U1-W_RX0(IO3)-Pad25)") (class "Default")
      (node (ref "U1") (pin "25") (pinfunction "W_RX0(IO3)_25") (pintype "unspecified+no_connect"))
    )
    (net (code "60") (name "unconnected-(U1-W_TX0(IO1)-Pad26)") (class "Default")
      (node (ref "U1") (pin "26") (pinfunction "W_TX0(IO1)_26") (pintype "unspecified+no_connect"))
    )
  )
)
